# devkit-r1.net
KiCad netlist of a schematic drawn in EAGLE
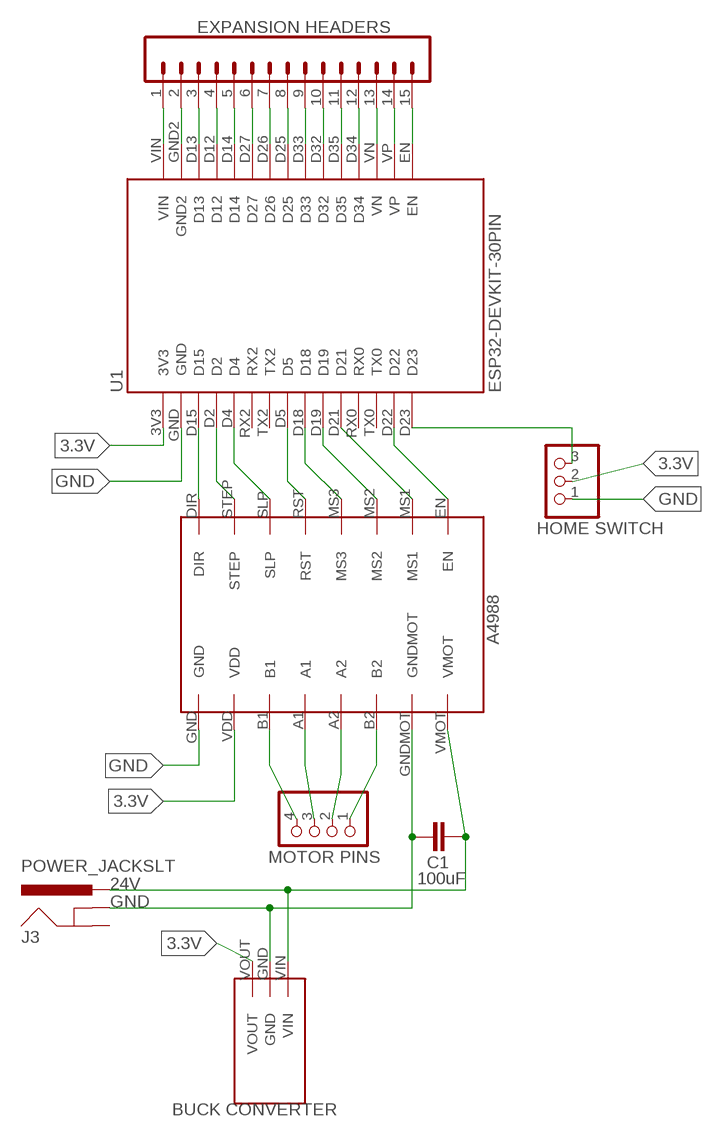
[diagram p0: schematic, sheet 1]

(export (version "E")
  (design (tool "Eeschema 10.0.6"))
  (components
    (comp (ref "BUCK")
      (value "BUCK-CONVERTERBUCK-CONVERTER")
      (footprint "eagle-import:BUCK-CONVERTER")
      (fields (field (name "LABEL") "BUCK CONVERTER"))
      (libsource (lib "eagle-import") (part "BUCK-CONVERTERBUCK-CONVERTER"))
    )
    (comp (ref "C1")
      (value "C2,5-3")
      (footprint "eagle-import:C2.5-3")
      (fields (field (name "CAPACITANCE") "100uF"))
      (libsource (lib "eagle-import") (part "C2,5-3"))
    )
    (comp (ref "J1")
      (value "CONN_15")
      (footprint "eagle-import:1X15")
      (fields (field (name "TITLE") "EXPANSION HEADERS"))
      (libsource (lib "eagle-import") (part "CONN_15"))
    )
    (comp (ref "J3")
      (value "POWER_JACKSLT")
      (footprint "eagle-import:POWER_JACK_SLOT")
      (libsource (lib "eagle-import") (part "POWER_JACKSLT"))
    )
    (comp (ref "JP1")
      (value "PINHD-1X4")
      (footprint "eagle-import:1X04")
      (fields (field (name "TITLE") "MOTOR PINS"))
      (libsource (lib "eagle-import") (part "PINHD-1X4"))
    )
    (comp (ref "JP2")
      (value "PINHD-1X3")
      (footprint "eagle-import:1X03")
      (fields (field (name "TITLE") "HOME SWITCH"))
      (libsource (lib "eagle-import") (part "PINHD-1X3"))
    )
    (comp (ref "U$1")
      (value "A4988A4988")
      (footprint "eagle-import:A4988")
      (fields (field (name "TITLE") "A4988"))
      (libsource (lib "eagle-import") (part "A4988A4988"))
    )
    (comp (ref "U1")
      (value "ESP32-DEVKIT-30PIN")
      (footprint "eagle-import:ESP32-DEVKIT-30PIN")
      (fields (field (name "MF") "Espressif Systems") (field (name "MP") "ESP32-DEVKITC-32D"))
      (libsource (lib "eagle-import") (part "ESP32-DEVKIT-30PIN"))
    )
  )
  (nets
    (net (code "1") (name "/24V") (class "Default")
      (node (ref "BUCK") (pin "VIN") (pinfunction "VIN_VIN") (pintype "bidirectional"))
      (node (ref "C1") (pin "2") (pinfunction "2_2") (pintype "passive"))
      (node (ref "J3") (pin "PWR") (pinfunction "PWR_PWR") (pintype "bidirectional"))
      (node (ref "U$1") (pin "VMOT") (pinfunction "VMOT_VMOT") (pintype "input"))
    )
    (net (code "2") (name "/TX0") (class "Default")
      (node (ref "U1") (pin "TX0") (pinfunction "TX0_TX0") (pintype "power_in"))
    )
    (net (code "3") (name "3.3V") (class "Default")
      (node (ref "BUCK") (pin "VOUT") (pinfunction "VOUT_VOUT") (pintype "bidirectional"))
      (node (ref "JP2") (pin "2") (pinfunction "2_2") (pintype "passive"))
      (node (ref "U$1") (pin "VDD") (pinfunction "VDD_VDD") (pintype "bidirectional"))
      (node (ref "U1") (pin "3V3") (pinfunction "3V3_3V3") (pintype "input"))
    )
    (net (code "4") (name "GND") (class "Default")
      (node (ref "BUCK") (pin "GND") (pinfunction "GND_GND") (pintype "bidirectional"))
      (node (ref "C1") (pin "1") (pinfunction "1_1") (pintype "passive"))
      (node (ref "J3") (pin "GND@1") (pinfunction "GNDBREAK_GND@1") (pintype "bidirectional"))
      (node (ref "JP2") (pin "1") (pinfunction "1_1") (pintype "passive"))
      (node (ref "U$1") (pin "GND") (pinfunction "GND_GND") (pintype "power_in"))
      (node (ref "U$1") (pin "GNDMOT") (pinfunction "GNDMOT_GNDMOT") (pintype "power_in"))
      (node (ref "U1") (pin "GND") (pinfunction "GND_GND") (pintype "input"))
    )
    (net (code "5") (name "Net-(J1-Pad1)") (class "Default")
      (node (ref "J1") (pin "1") (pinfunction "1_1") (pintype "passive"))
      (node (ref "U1") (pin "VIN") (pinfunction "VIN_VIN") (pintype "bidirectional"))
    )
    (net (code "6") (name "Net-(J1-Pad2)") (class "Default")
      (node (ref "J1") (pin "2") (pinfunction "2_2") (pintype "passive"))
      (node (ref "U1") (pin "GND2") (pinfunction "GND2_GND2") (pintype "bidirectional"))
    )
    (net (code "7") (name "Net-(J1-Pad3)") (class "Default")
      (node (ref "J1") (pin "3") (pinfunction "3_3") (pintype "passive"))
      (node (ref "U1") (pin "D13") (pinfunction "D13_D13") (pintype "output"))
    )
    (net (code "8") (name "Net-(J1-Pad4)") (class "Default")
      (node (ref "J1") (pin "4") (pinfunction "4_4") (pintype "passive"))
      (node (ref "U1") (pin "D12") (pinfunction "D12_D12") (pintype "input"))
    )
    (net (code "9") (name "Net-(J1-Pad5)") (class "Default")
      (node (ref "J1") (pin "5") (pinfunction "5_5") (pintype "passive"))
      (node (ref "U1") (pin "D14") (pinfunction "D14_D14") (pintype "bidirectional"))
    )
    (net (code "10") (name "Net-(J1-Pad6)") (class "Default")
      (node (ref "J1") (pin "6") (pinfunction "6_6") (pintype "passive"))
      (node (ref "U1") (pin "D27") (pinfunction "D27_D27") (pintype "power_in"))
    )
    (net (code "11") (name "Net-(J1-Pad7)") (class "Default")
      (node (ref "J1") (pin "7") (pinfunction "7_7") (pintype "passive"))
      (node (ref "U1") (pin "D26") (pinfunction "D26_D26") (pintype "bidirectional"))
    )
    (net (code "12") (name "Net-(J1-Pad8)") (class "Default")
      (node (ref "J1") (pin "8") (pinfunction "8_8") (pintype "passive"))
      (node (ref "U1") (pin "D25") (pinfunction "D25_D25") (pintype "bidirectional"))
    )
    (net (code "13") (name "Net-(J1-Pad9)") (class "Default")
      (node (ref "J1") (pin "9") (pinfunction "9_9") (pintype "passive"))
      (node (ref "U1") (pin "D33") (pinfunction "D33_D33") (pintype "bidirectional"))
    )
    (net (code "14") (name "Net-(J1-Pad10)") (class "Default")
      (node (ref "J1") (pin "10") (pinfunction "10_10") (pintype "passive"))
      (node (ref "U1") (pin "D32") (pinfunction "D32_D32") (pintype "bidirectional"))
    )
    (net (code "15") (name "Net-(J1-Pad11)") (class "Default")
      (node (ref "J1") (pin "11") (pinfunction "11_11") (pintype "passive"))
      (node (ref "U1") (pin "D35") (pinfunction "D35_D35") (pintype "bidirectional"))
    )
    (net (code "16") (name "Net-(J1-Pad12)") (class "Default")
      (node (ref "J1") (pin "12") (pinfunction "12_12") (pintype "passive"))
      (node (ref "U1") (pin "D34") (pinfunction "D34_D34") (pintype "bidirectional"))
    )
    (net (code "17") (name "Net-(J1-Pad13)") (class "Default")
      (node (ref "J1") (pin "13") (pinfunction "13_13") (pintype "passive"))
      (node (ref "U1") (pin "VN") (pinfunction "VN_VN") (pintype "bidirectional"))
    )
    (net (code "18") (name "Net-(J1-Pad14)") (class "Default")
      (node (ref "J1") (pin "14") (pinfunction "14_14") (pintype "passive"))
      (node (ref "U1") (pin "VP") (pinfunction "VP_VP") (pintype "bidirectional"))
    )
    (net (code "19") (name "Net-(J1-Pad15)") (class "Default")
      (node (ref "J1") (pin "15") (pinfunction "15_15") (pintype "passive"))
      (node (ref "U1") (pin "EN") (pinfunction "EN_EN") (pintype "bidirectional"))
    )
    (net (code "20") (name "Net-(JP1-Pad1)") (class "Default")
      (node (ref "JP1") (pin "1") (pinfunction "1_1") (pintype "passive"))
      (node (ref "U$1") (pin "B2") (pinfunction "B2_B2") (pintype "output"))
    )
    (net (code "21") (name "Net-(JP1-Pad2)") (class "Default")
      (node (ref "JP1") (pin "2") (pinfunction "2_2") (pintype "passive"))
      (node (ref "U$1") (pin "A2") (pinfunction "A2_A2") (pintype "output"))
    )
    (net (code "22") (name "Net-(JP1-Pad3)") (class "Default")
      (node (ref "JP1") (pin "3") (pinfunction "3_3") (pintype "passive"))
      (node (ref "U$1") (pin "A1") (pinfunction "A1_A1") (pintype "output"))
    )
    (net (code "23") (name "Net-(JP1-Pad4)") (class "Default")
      (node (ref "JP1") (pin "4") (pinfunction "4_4") (pintype "passive"))
      (node (ref "U$1") (pin "B1") (pinfunction "B1_B1") (pintype "output"))
    )
    (net (code "24") (name "Net-(JP2-Pad3)") (class "Default")
      (node (ref "JP2") (pin "3") (pinfunction "3_3") (pintype "passive"))
      (node (ref "U1") (pin "D23") (pinfunction "D23_D23") (pintype "bidirectional"))
    )
    (net (code "25") (name "Net-(U$1-PadDIR)") (class "Default")
      (node (ref "U$1") (pin "DIR") (pinfunction "DIR_DIR") (pintype "input"))
      (node (ref "U1") (pin "D15") (pinfunction "D15_D15") (pintype "input"))
    )
    (net (code "26") (name "Net-(U$1-PadEN)") (class "Default")
      (node (ref "U$1") (pin "EN") (pinfunction "EN_EN") (pintype "input"))
      (node (ref "U1") (pin "D22") (pinfunction "D22_D22") (pintype "bidirectional"))
    )
    (net (code "27") (name "Net-(U$1-PadMS1)") (class "Default")
      (node (ref "U$1") (pin "MS1") (pinfunction "MS1_MS1") (pintype "input"))
      (node (ref "U1") (pin "D21") (pinfunction "D21_D21") (pintype "bidirectional"))
    )
    (net (code "28") (name "Net-(U$1-PadMS2)") (class "Default")
      (node (ref "U$1") (pin "MS2") (pinfunction "MS2_MS2") (pintype "input"))
      (node (ref "U1") (pin "D19") (pinfunction "D19_D19") (pintype "bidirectional"))
    )
    (net (code "29") (name "Net-(U$1-PadMS3)") (class "Default")
      (node (ref "U$1") (pin "MS3") (pinfunction "MS3_MS3") (pintype "input"))
      (node (ref "U1") (pin "D18") (pinfunction "D18_D18") (pintype "bidirectional"))
    )
    (net (code "30") (name "Net-(U$1-PadRST)") (class "Default")
      (node (ref "U$1") (pin "RST") (pinfunction "RST_RST") (pintype "input"))
      (node (ref "U1") (pin "D5") (pinfunction "D5_D5") (pintype "bidirectional"))
    )
    (net (code "31") (name "Net-(U$1-PadSLP)") (class "Default")
      (node (ref "U$1") (pin "SLP") (pinfunction "SLP_SLP") (pintype "input"))
      (node (ref "U1") (pin "D4") (pinfunction "D4_D4") (pintype "bidirectional"))
    )
    (net (code "32") (name "Net-(U$1-PadSTEP)") (class "Default")
      (node (ref "U$1") (pin "STEP") (pinfunction "STEP_STEP") (pintype "input"))
      (node (ref "U1") (pin "D2") (pinfunction "D2_D2") (pintype "bidirectional"))
    )
    (net (code "33") (name "unconnected-(J3-GND-PadGND@2)") (class "Default")
      (node (ref "J3") (pin "GND@2") (pinfunction "GND_GND@2") (pintype "bidirectional"))
    )
    (net (code "34") (name "unconnected-(U1-PadRX0)") (class "Default")
      (node (ref "U1") (pin "RX0") (pinfunction "RX0_RX0") (pintype "bidirectional"))
    )
    (net (code "35") (name "unconnected-(U1-PadRX2)") (class "Default")
      (node (ref "U1") (pin "RX2") (pinfunction "RX2_RX2") (pintype "bidirectional"))
    )
    (net (code "36") (name "unconnected-(U1-PadTX2)") (class "Default")
      (node (ref "U1") (pin "TX2") (pinfunction "TX2_TX2") (pintype "bidirectional"))
    )
  )
)
